# UA18_Dash.net
KiCad netlist of a schematic drawn in EAGLE
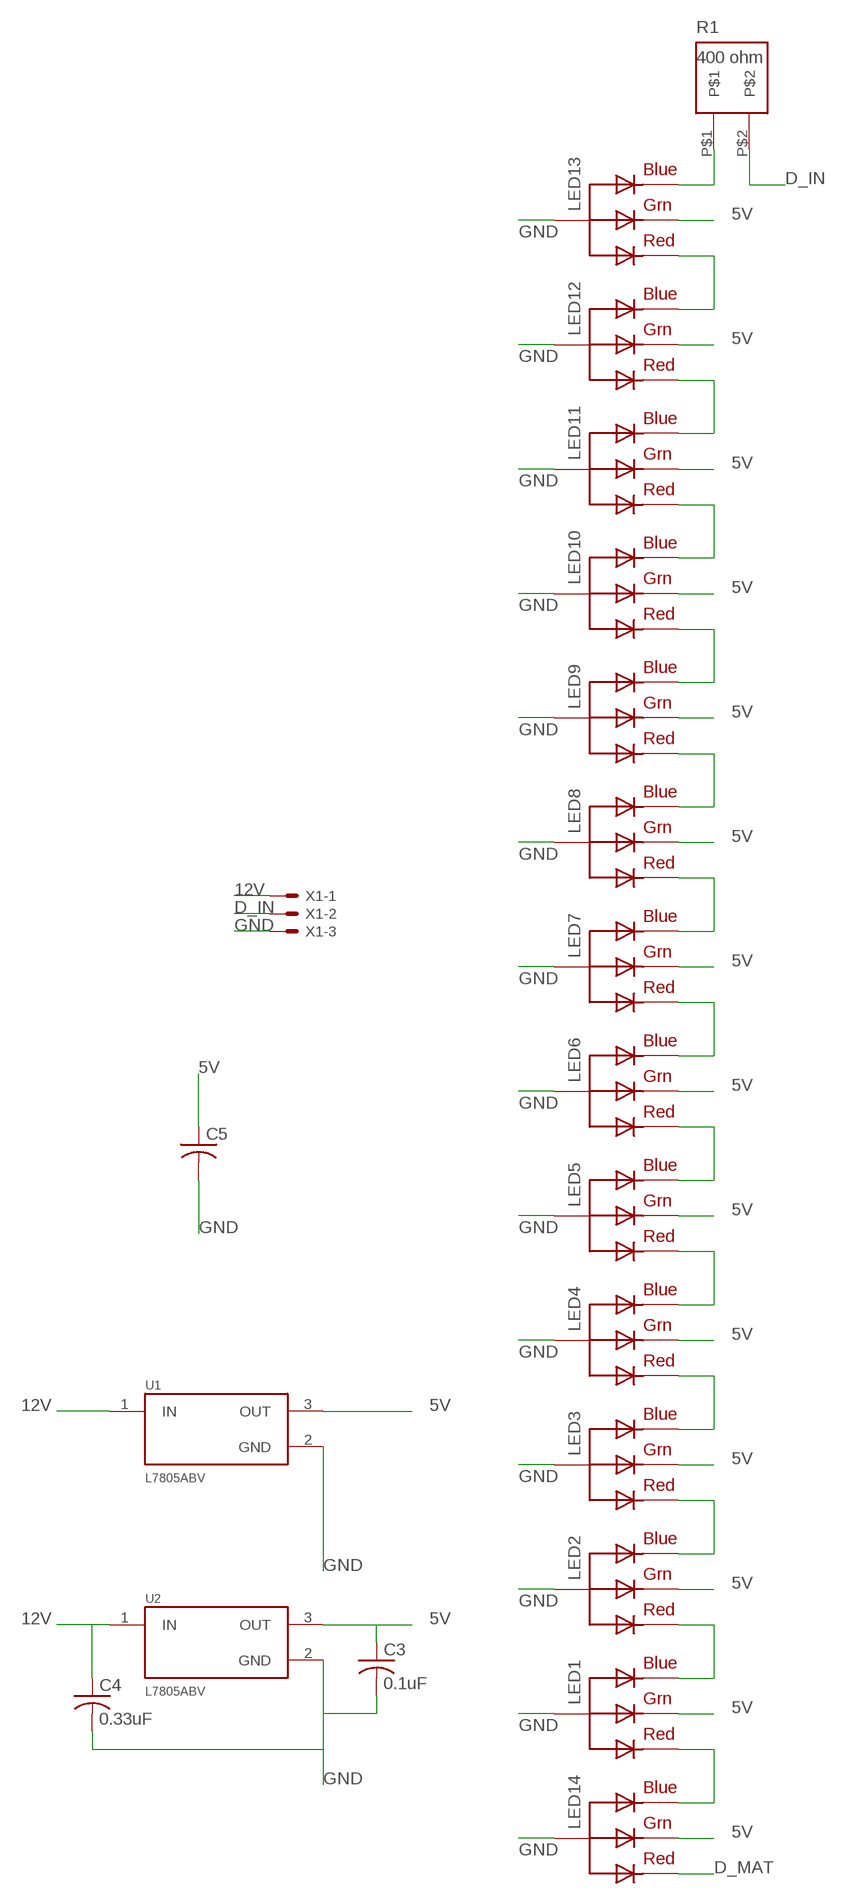
[diagram p0: schematic, sheet 1]
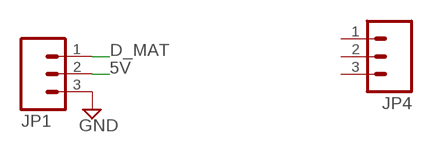
[diagram p1: schematic, sheet 2]

(export (version "E")
  (design (tool "Eeschema 10.0.6"))
  (components
    (comp (ref "C3")
      (value "0.1uF")
      (footprint "eagle-import:C050-024X044")
      (libsource (lib "eagle-import") (part "C-US050-024X044"))
    )
    (comp (ref "C4")
      (value "0.33uF")
      (footprint "eagle-import:C050-024X044")
      (libsource (lib "eagle-import") (part "C-US050-024X044"))
    )
    (comp (ref "C5")
      (value "C-US275-093X316")
      (footprint "eagle-import:C275-093X316")
      (libsource (lib "eagle-import") (part "C-US275-093X316"))
    )
    (comp (ref "LED1")
      (value "RGBLED_CA-5MM")
      (footprint "eagle-import:LED5MMRGB")
      (libsource (lib "eagle-import") (part "RGBLED_CA-5MM"))
    )
    (comp (ref "LED2")
      (value "RGBLED_CA-5MM")
      (footprint "eagle-import:LED5MMRGB")
      (libsource (lib "eagle-import") (part "RGBLED_CA-5MM"))
    )
    (comp (ref "LED3")
      (value "RGBLED_CA-5MM")
      (footprint "eagle-import:LED5MMRGB")
      (libsource (lib "eagle-import") (part "RGBLED_CA-5MM"))
    )
    (comp (ref "LED4")
      (value "RGBLED_CA-5MM")
      (footprint "eagle-import:LED5MMRGB")
      (libsource (lib "eagle-import") (part "RGBLED_CA-5MM"))
    )
    (comp (ref "LED5")
      (value "RGBLED_CA-5MM")
      (footprint "eagle-import:LED5MMRGB")
      (libsource (lib "eagle-import") (part "RGBLED_CA-5MM"))
    )
    (comp (ref "LED6")
      (value "RGBLED_CA-5MM")
      (footprint "eagle-import:LED5MMRGB")
      (libsource (lib "eagle-import") (part "RGBLED_CA-5MM"))
    )
    (comp (ref "LED7")
      (value "RGBLED_CA-5MM")
      (footprint "eagle-import:LED5MMRGB")
      (libsource (lib "eagle-import") (part "RGBLED_CA-5MM"))
    )
    (comp (ref "LED8")
      (value "RGBLED_CA-5MM")
      (footprint "eagle-import:LED5MMRGB")
      (libsource (lib "eagle-import") (part "RGBLED_CA-5MM"))
    )
    (comp (ref "LED9")
      (value "RGBLED_CA-5MM")
      (footprint "eagle-import:LED5MMRGB")
      (libsource (lib "eagle-import") (part "RGBLED_CA-5MM"))
    )
    (comp (ref "LED10")
      (value "RGBLED_CA-5MM")
      (footprint "eagle-import:LED5MMRGB")
      (libsource (lib "eagle-import") (part "RGBLED_CA-5MM"))
    )
    (comp (ref "LED11")
      (value "RGBLED_CA-5MM")
      (footprint "eagle-import:LED5MMRGB")
      (libsource (lib "eagle-import") (part "RGBLED_CA-5MM"))
    )
    (comp (ref "LED12")
      (value "RGBLED_CA-5MM")
      (footprint "eagle-import:LED5MMRGB")
      (libsource (lib "eagle-import") (part "RGBLED_CA-5MM"))
    )
    (comp (ref "LED13")
      (value "RGBLED_CA-5MM")
      (footprint "eagle-import:LED5MMRGB")
      (libsource (lib "eagle-import") (part "RGBLED_CA-5MM"))
    )
    (comp (ref "LED14")
      (value "RGBLED_CA-5MM")
      (footprint "eagle-import:LED5MMRGB")
      (libsource (lib "eagle-import") (part "RGBLED_CA-5MM"))
    )
    (comp (ref "R1")
      (value "400 ohm")
      (footprint "eagle-import:TO-126")
      (libsource (lib "eagle-import") (part "684-MP915-400"))
    )
    (comp (ref "U1")
      (value "L7805ABV")
      (footprint "eagle-import:TO254P460X1020X1945-3P")
      (fields (field (name "MF") "STMicroelectronics"))
      (libsource (lib "eagle-import") (part "L7805ABV"))
    )
    (comp (ref "U2")
      (value "L7805ABV")
      (footprint "eagle-import:TO254P460X1020X1945-3P")
      (fields (field (name "MF") "STMicroelectronics"))
      (libsource (lib "eagle-import") (part "L7805ABV"))
    )
    (comp (ref "X1")
      (value "KK-156-3")
      (footprint "eagle-import:KK-156-3")
      (fields (field (name "MF") "MOLEX"))
      (libsource (lib "eagle-import") (part "KK-156-3"))
    )
    (comp (ref "JP1")
      (value "M03PTH")
      (footprint "eagle-import:1X03")
      (libsource (lib "eagle-import") (part "M03PTH"))
    )
    (comp (ref "JP4")
      (value "M03PTH")
      (footprint "eagle-import:1X03")
      (libsource (lib "eagle-import") (part "M03PTH"))
    )
  )
  (nets
    (net (code "1") (name "5V") (class "Default")
      (node (ref "C3") (pin "1") (pinfunction "1_1") (pintype "passive"))
      (node (ref "C5") (pin "1") (pinfunction "1_1") (pintype "passive"))
      (node (ref "JP1") (pin "2") (pinfunction "2_2") (pintype "passive"))
      (node (ref "LED1") (pin "3") (pinfunction "GREEN_3") (pintype "bidirectional"))
      (node (ref "LED10") (pin "3") (pinfunction "GREEN_3") (pintype "bidirectional"))
      (node (ref "LED11") (pin "3") (pinfunction "GREEN_3") (pintype "bidirectional"))
      (node (ref "LED12") (pin "3") (pinfunction "GREEN_3") (pintype "bidirectional"))
      (node (ref "LED13") (pin "3") (pinfunction "GREEN_3") (pintype "bidirectional"))
      (node (ref "LED14") (pin "3") (pinfunction "GREEN_3") (pintype "bidirectional"))
      (node (ref "LED2") (pin "3") (pinfunction "GREEN_3") (pintype "bidirectional"))
      (node (ref "LED3") (pin "3") (pinfunction "GREEN_3") (pintype "bidirectional"))
      (node (ref "LED4") (pin "3") (pinfunction "GREEN_3") (pintype "bidirectional"))
      (node (ref "LED5") (pin "3") (pinfunction "GREEN_3") (pintype "bidirectional"))
      (node (ref "LED6") (pin "3") (pinfunction "GREEN_3") (pintype "bidirectional"))
      (node (ref "LED7") (pin "3") (pinfunction "GREEN_3") (pintype "bidirectional"))
      (node (ref "LED8") (pin "3") (pinfunction "GREEN_3") (pintype "bidirectional"))
      (node (ref "LED9") (pin "3") (pinfunction "GREEN_3") (pintype "bidirectional"))
      (node (ref "U1") (pin "3") (pinfunction "OUT_3") (pintype "output"))
      (node (ref "U2") (pin "3") (pinfunction "OUT_3") (pintype "output"))
    )
    (net (code "2") (name "12V") (class "Default")
      (node (ref "C4") (pin "1") (pinfunction "1_1") (pintype "passive"))
      (node (ref "U1") (pin "1") (pinfunction "IN_1") (pintype "input"))
      (node (ref "U2") (pin "1") (pinfunction "IN_1") (pintype "input"))
      (node (ref "X1") (pin "1") (pinfunction "S_1") (pintype "passive"))
    )
    (net (code "3") (name "DO_L12") (class "Default")
      (node (ref "LED1") (pin "1") (pinfunction "RED_1") (pintype "bidirectional"))
      (node (ref "LED1") (pin "4") (pinfunction "BLUE_4") (pintype "bidirectional"))
      (node (ref "LED14") (pin "4") (pinfunction "BLUE_4") (pintype "bidirectional"))
      (node (ref "LED2") (pin "1") (pinfunction "RED_1") (pintype "bidirectional"))
    )
    (net (code "4") (name "D_IN") (class "Default")
      (node (ref "R1") (pin "P$2") (pinfunction "P$2_P$2") (pintype "bidirectional"))
      (node (ref "X1") (pin "2") (pinfunction "S_2") (pintype "passive"))
    )
    (net (code "5") (name "D_MAT") (class "Default")
      (node (ref "JP1") (pin "1") (pinfunction "1_1") (pintype "passive"))
      (node (ref "LED14") (pin "1") (pinfunction "RED_1") (pintype "bidirectional"))
    )
    (net (code "6") (name "GND") (class "Default")
      (node (ref "C3") (pin "2") (pinfunction "2_2") (pintype "passive"))
      (node (ref "C4") (pin "2") (pinfunction "2_2") (pintype "passive"))
      (node (ref "C5") (pin "2") (pinfunction "2_2") (pintype "passive"))
      (node (ref "JP1") (pin "3") (pinfunction "3_3") (pintype "passive"))
      (node (ref "LED1") (pin "2") (pinfunction "VCC_2") (pintype "bidirectional"))
      (node (ref "LED10") (pin "2") (pinfunction "VCC_2") (pintype "bidirectional"))
      (node (ref "LED11") (pin "2") (pinfunction "VCC_2") (pintype "bidirectional"))
      (node (ref "LED12") (pin "2") (pinfunction "VCC_2") (pintype "bidirectional"))
      (node (ref "LED13") (pin "2") (pinfunction "VCC_2") (pintype "bidirectional"))
      (node (ref "LED14") (pin "2") (pinfunction "VCC_2") (pintype "bidirectional"))
      (node (ref "LED2") (pin "2") (pinfunction "VCC_2") (pintype "bidirectional"))
      (node (ref "LED3") (pin "2") (pinfunction "VCC_2") (pintype "bidirectional"))
      (node (ref "LED4") (pin "2") (pinfunction "VCC_2") (pintype "bidirectional"))
      (node (ref "LED5") (pin "2") (pinfunction "VCC_2") (pintype "bidirectional"))
      (node (ref "LED6") (pin "2") (pinfunction "VCC_2") (pintype "bidirectional"))
      (node (ref "LED7") (pin "2") (pinfunction "VCC_2") (pintype "bidirectional"))
      (node (ref "LED8") (pin "2") (pinfunction "VCC_2") (pintype "bidirectional"))
      (node (ref "LED9") (pin "2") (pinfunction "VCC_2") (pintype "bidirectional"))
      (node (ref "U1") (pin "2") (pinfunction "GND_2") (pintype "power_in"))
      (node (ref "U2") (pin "2") (pinfunction "GND_2") (pintype "power_in"))
      (node (ref "X1") (pin "3") (pinfunction "S_3") (pintype "passive"))
    )
    (net (code "7") (name "Net-(LED2-BLUE)") (class "Default")
      (node (ref "LED2") (pin "4") (pinfunction "BLUE_4") (pintype "bidirectional"))
      (node (ref "LED3") (pin "1") (pinfunction "RED_1") (pintype "bidirectional"))
    )
    (net (code "8") (name "Net-(LED3-BLUE)") (class "Default")
      (node (ref "LED3") (pin "4") (pinfunction "BLUE_4") (pintype "bidirectional"))
      (node (ref "LED4") (pin "1") (pinfunction "RED_1") (pintype "bidirectional"))
    )
    (net (code "9") (name "Net-(LED4-BLUE)") (class "Default")
      (node (ref "LED4") (pin "4") (pinfunction "BLUE_4") (pintype "bidirectional"))
      (node (ref "LED5") (pin "1") (pinfunction "RED_1") (pintype "bidirectional"))
    )
    (net (code "10") (name "Net-(LED5-BLUE)") (class "Default")
      (node (ref "LED5") (pin "4") (pinfunction "BLUE_4") (pintype "bidirectional"))
      (node (ref "LED6") (pin "1") (pinfunction "RED_1") (pintype "bidirectional"))
    )
    (net (code "11") (name "Net-(LED6-BLUE)") (class "Default")
      (node (ref "LED6") (pin "4") (pinfunction "BLUE_4") (pintype "bidirectional"))
      (node (ref "LED7") (pin "1") (pinfunction "RED_1") (pintype "bidirectional"))
    )
    (net (code "12") (name "Net-(LED7-BLUE)") (class "Default")
      (node (ref "LED7") (pin "4") (pinfunction "BLUE_4") (pintype "bidirectional"))
      (node (ref "LED8") (pin "1") (pinfunction "RED_1") (pintype "bidirectional"))
    )
    (net (code "13") (name "Net-(LED8-BLUE)") (class "Default")
      (node (ref "LED8") (pin "4") (pinfunction "BLUE_4") (pintype "bidirectional"))
      (node (ref "LED9") (pin "1") (pinfunction "RED_1") (pintype "bidirectional"))
    )
    (net (code "14") (name "Net-(LED10-BLUE)") (class "Default")
      (node (ref "LED10") (pin "4") (pinfunction "BLUE_4") (pintype "bidirectional"))
      (node (ref "LED11") (pin "1") (pinfunction "RED_1") (pintype "bidirectional"))
    )
    (net (code "15") (name "Net-(LED10-RED)") (class "Default")
      (node (ref "LED10") (pin "1") (pinfunction "RED_1") (pintype "bidirectional"))
      (node (ref "LED9") (pin "4") (pinfunction "BLUE_4") (pintype "bidirectional"))
    )
    (net (code "16") (name "Net-(LED11-BLUE)") (class "Default")
      (node (ref "LED11") (pin "4") (pinfunction "BLUE_4") (pintype "bidirectional"))
      (node (ref "LED12") (pin "1") (pinfunction "RED_1") (pintype "bidirectional"))
    )
    (net (code "17") (name "Net-(LED12-BLUE)") (class "Default")
      (node (ref "LED12") (pin "4") (pinfunction "BLUE_4") (pintype "bidirectional"))
      (node (ref "LED13") (pin "1") (pinfunction "RED_1") (pintype "bidirectional"))
    )
    (net (code "18") (name "Net-(LED13-BLUE)") (class "Default")
      (node (ref "LED13") (pin "4") (pinfunction "BLUE_4") (pintype "bidirectional"))
      (node (ref "R1") (pin "P$1") (pinfunction "P$1_P$1") (pintype "bidirectional"))
    )
    (net (code "19") (name "unconnected-(JP4-Pad1)") (class "Default")
      (node (ref "JP4") (pin "1") (pinfunction "1_1") (pintype "passive"))
    )
    (net (code "20") (name "unconnected-(JP4-Pad2)") (class "Default")
      (node (ref "JP4") (pin "2") (pinfunction "2_2") (pintype "passive"))
    )
    (net (code "21") (name "unconnected-(JP4-Pad3)") (class "Default")
      (node (ref "JP4") (pin "3") (pinfunction "3_3") (pintype "passive"))
    )
  )
)
